# 13_-_ETHERNET_PHY.net
KiCad netlist of a schematic drawn in Altium Designer
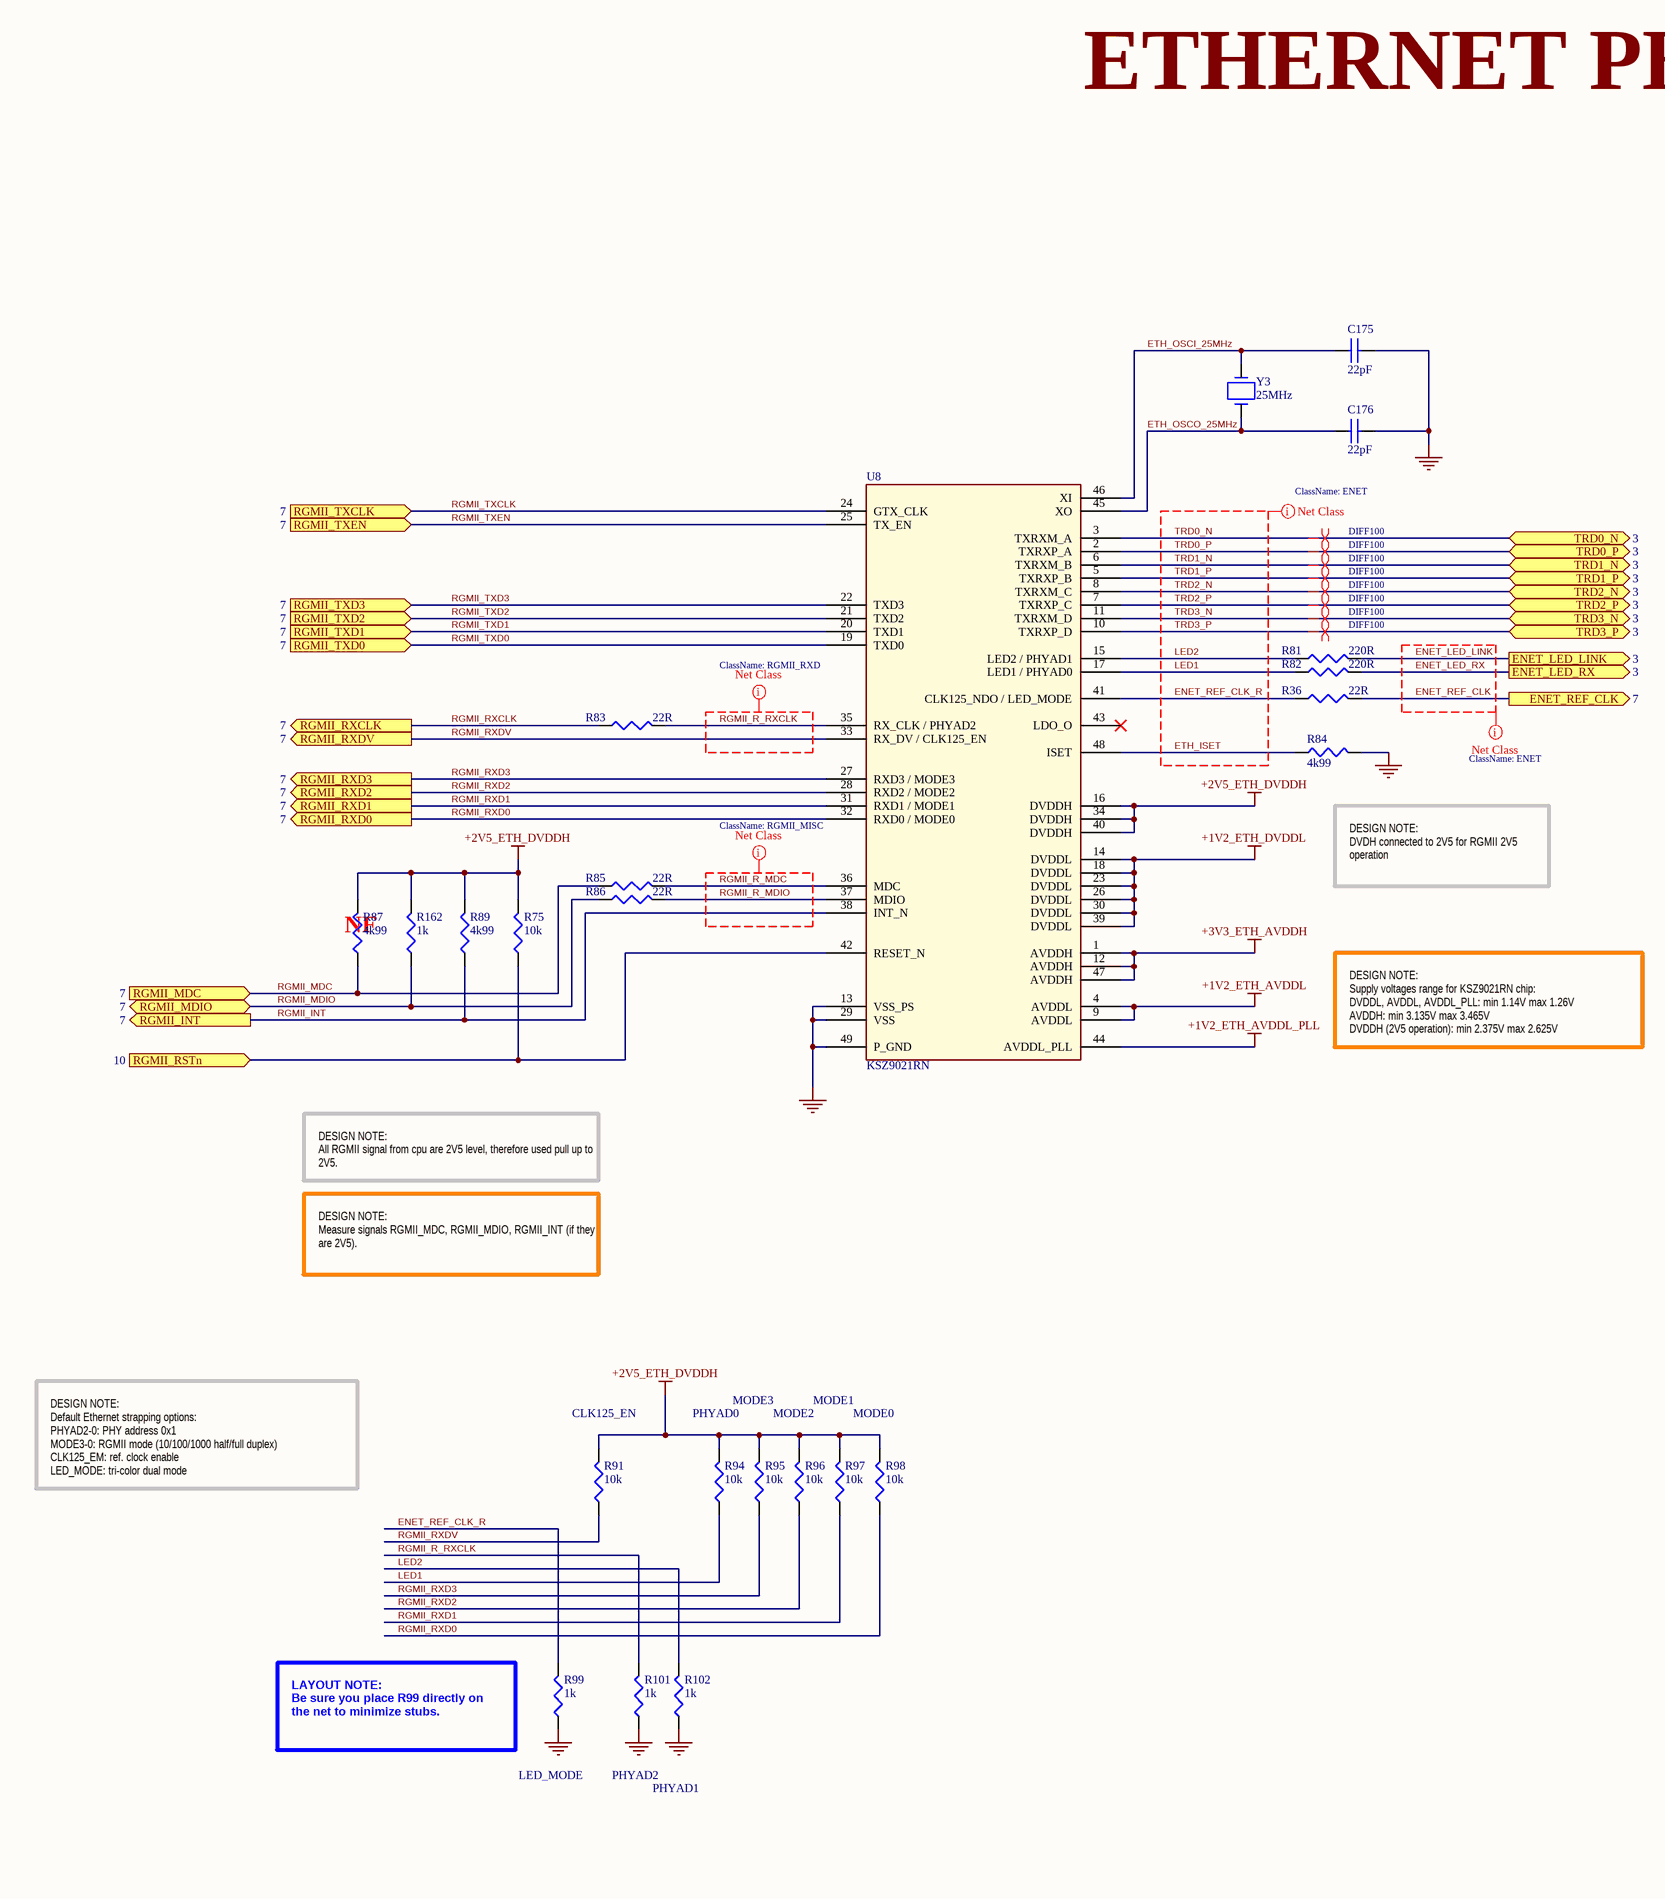
[diagram p0: [13] - ETHERNET PHY.SchDoc, left]
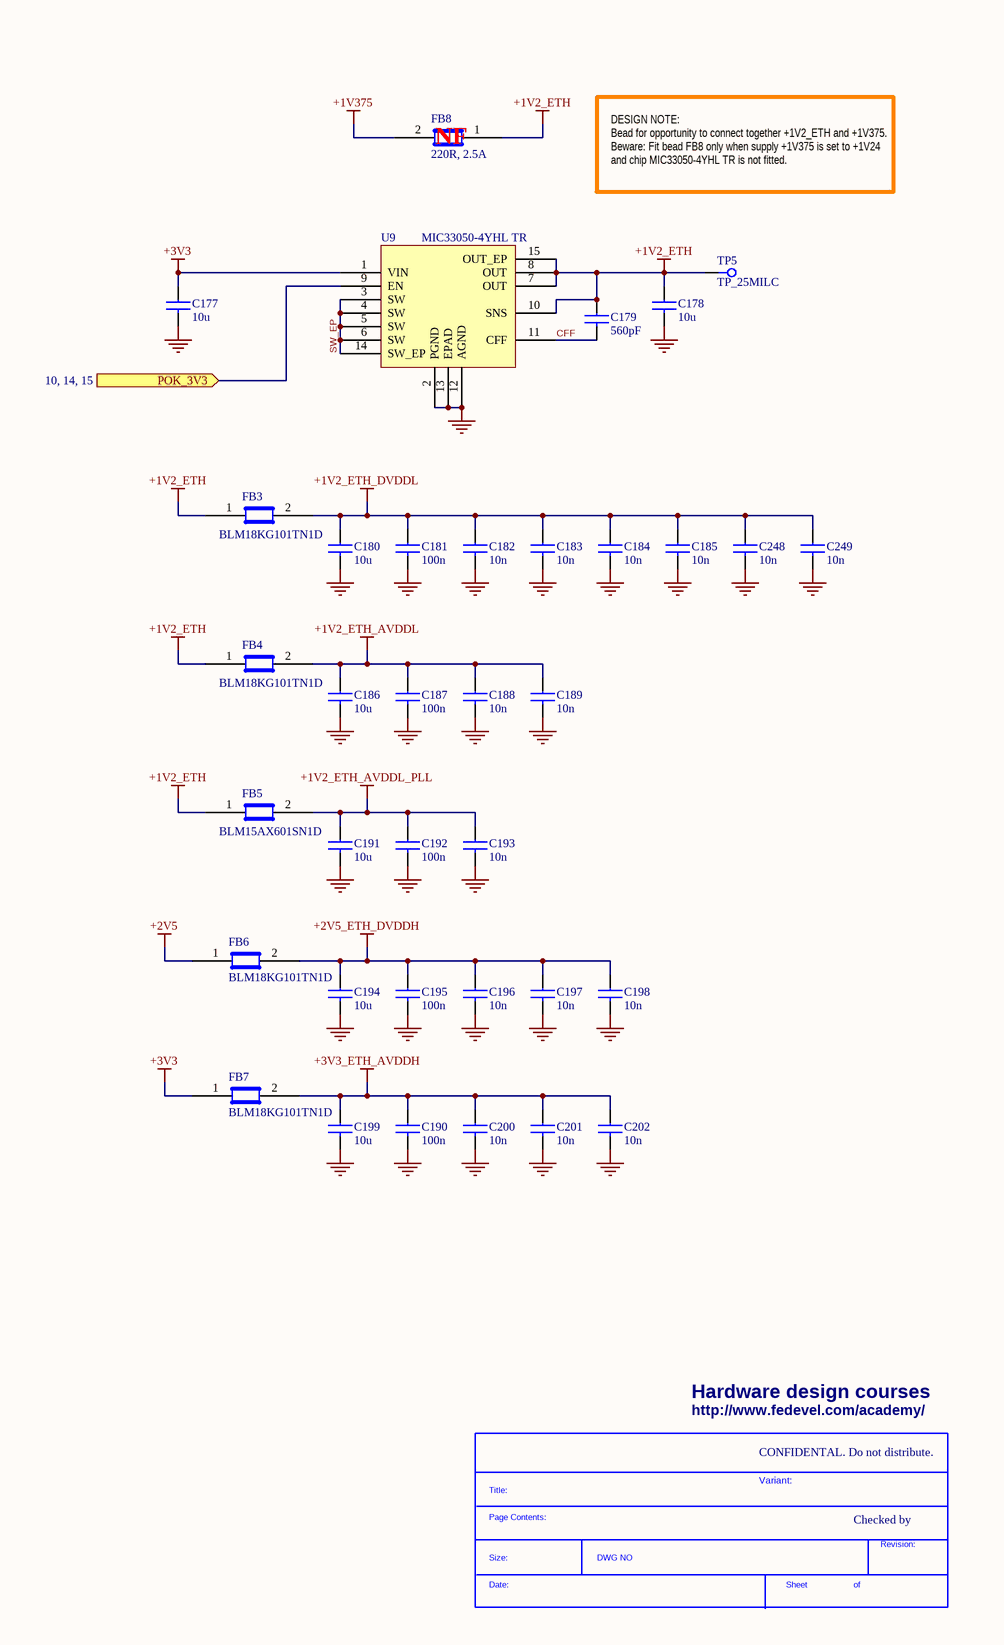
[diagram p1: [13] - ETHERNET PHY.SchDoc, right]

(export (version "E")
  (design (tool "Eeschema 10.0.6"))
  (components
    (comp (ref "C175")
      (value "22pF")
      (footprint "C0402")
      (description "CAP CER 22PF 50V C0G 5% 0402")
      (fields
        (field (name "MANUFACTURER") "TDK Corporation")
        (field (name "MANUFACTURER PART NUMBER") "C1005C0G1H220J")
      )
      (libsource (lib "iMX6 Rex_V1I1") (part "C1005C0G1H220J"))
    )
    (comp (ref "C176")
      (value "22pF")
      (footprint "C0402")
      (description "CAP CER 22PF 50V C0G 5% 0402")
      (fields
        (field (name "MANUFACTURER") "TDK Corporation")
        (field (name "MANUFACTURER PART NUMBER") "C1005C0G1H220J")
      )
      (libsource (lib "iMX6 Rex_V1I1") (part "C1005C0G1H220J"))
    )
    (comp (ref "C177")
      (value "10u")
      (footprint "C0603")
      (description "CAP CER 10UF 6.3V X5R 20% 0603")
      (fields
        (field (name "MANUFACTURER") "TDK Corporation")
        (field (name "MANUFACTURER PART NUMBER") "C1608X5R0J106M")
      )
      (libsource (lib "iMX6 Rex_V1I1") (part "C1608X5R0J106M"))
    )
    (comp (ref "C178")
      (value "10u")
      (footprint "C0603")
      (description "CAP CER 10UF 6.3V X5R 20% 0603")
      (fields
        (field (name "MANUFACTURER") "TDK Corporation")
        (field (name "MANUFACTURER PART NUMBER") "C1608X5R0J106M")
      )
      (libsource (lib "iMX6 Rex_V1I1") (part "C1608X5R0J106M"))
    )
    (comp (ref "C179")
      (value "560pF")
      (footprint "C0402")
      (description "CAP CER 560PF 50V C0G 0402")
      (fields
        (field (name "MANUFACTURER") "Murata Electronics North America")
        (field (name "MANUFACTURER PART NUMBER") "GRM1555C1H561JA01D")
      )
      (libsource (lib "iMX6 Rex_V1I1") (part "GRM1555C1H561JA01D"))
    )
    (comp (ref "C180")
      (value "10u")
      (footprint "C0603")
      (description "CAP CER 10UF 6.3V X5R 20% 0603")
      (fields
        (field (name "MANUFACTURER") "TDK Corporation")
        (field (name "MANUFACTURER PART NUMBER") "C1608X5R0J106M")
      )
      (libsource (lib "iMX6 Rex_V1I1") (part "C1608X5R0J106M"))
    )
    (comp (ref "C181")
      (value "100n")
      (footprint "C0402")
      (description "CAP CER .10UF 50V X5R 10% 0402")
      (fields
        (field (name "MANUFACTURER") "TDK Corporation")
        (field (name "MANUFACTURER PART NUMBER") "C1005X5R1H104K")
      )
      (libsource (lib "iMX6 Rex_V1I1") (part "C1005X5R1H104K"))
    )
    (comp (ref "C182")
      (value "10n")
      (footprint "C0402")
      (description "CAP CER 10000PF 16V X7R 10% 0402")
      (fields
        (field (name "MANUFACTURER") "TDK Corporation")
        (field (name "MANUFACTURER PART NUMBER") "C1005X7R1C103K")
      )
      (libsource (lib "iMX6 Rex_V1I1") (part "C1005X7R1C103K"))
    )
    (comp (ref "C183")
      (value "10n")
      (footprint "C0402")
      (description "CAP CER 10000PF 16V X7R 10% 0402")
      (fields
        (field (name "MANUFACTURER") "TDK Corporation")
        (field (name "MANUFACTURER PART NUMBER") "C1005X7R1C103K")
      )
      (libsource (lib "iMX6 Rex_V1I1") (part "C1005X7R1C103K"))
    )
    (comp (ref "C184")
      (value "10n")
      (footprint "C0402")
      (description "CAP CER 10000PF 16V X7R 10% 0402")
      (fields
        (field (name "MANUFACTURER") "TDK Corporation")
        (field (name "MANUFACTURER PART NUMBER") "C1005X7R1C103K")
      )
      (libsource (lib "iMX6 Rex_V1I1") (part "C1005X7R1C103K"))
    )
    (comp (ref "C185")
      (value "10n")
      (footprint "C0402")
      (description "CAP CER 10000PF 16V X7R 10% 0402")
      (fields
        (field (name "MANUFACTURER") "TDK Corporation")
        (field (name "MANUFACTURER PART NUMBER") "C1005X7R1C103K")
      )
      (libsource (lib "iMX6 Rex_V1I1") (part "C1005X7R1C103K"))
    )
    (comp (ref "C186")
      (value "10u")
      (footprint "C0603")
      (description "CAP CER 10UF 6.3V X5R 20% 0603")
      (fields
        (field (name "MANUFACTURER") "TDK Corporation")
        (field (name "MANUFACTURER PART NUMBER") "C1608X5R0J106M")
      )
      (libsource (lib "iMX6 Rex_V1I1") (part "C1608X5R0J106M"))
    )
    (comp (ref "C187")
      (value "100n")
      (footprint "C0402")
      (description "CAP CER .10UF 50V X5R 10% 0402")
      (fields
        (field (name "MANUFACTURER") "TDK Corporation")
        (field (name "MANUFACTURER PART NUMBER") "C1005X5R1H104K")
      )
      (libsource (lib "iMX6 Rex_V1I1") (part "C1005X5R1H104K"))
    )
    (comp (ref "C188")
      (value "10n")
      (footprint "C0402")
      (description "CAP CER 10000PF 16V X7R 10% 0402")
      (fields
        (field (name "MANUFACTURER") "TDK Corporation")
        (field (name "MANUFACTURER PART NUMBER") "C1005X7R1C103K")
      )
      (libsource (lib "iMX6 Rex_V1I1") (part "C1005X7R1C103K"))
    )
    (comp (ref "C189")
      (value "10n")
      (footprint "C0402")
      (description "CAP CER 10000PF 16V X7R 10% 0402")
      (fields
        (field (name "MANUFACTURER") "TDK Corporation")
        (field (name "MANUFACTURER PART NUMBER") "C1005X7R1C103K")
      )
      (libsource (lib "iMX6 Rex_V1I1") (part "C1005X7R1C103K"))
    )
    (comp (ref "C190")
      (value "100n")
      (footprint "C0402")
      (description "CAP CER .10UF 50V X5R 10% 0402")
      (fields
        (field (name "MANUFACTURER") "TDK Corporation")
        (field (name "MANUFACTURER PART NUMBER") "C1005X5R1H104K")
      )
      (libsource (lib "iMX6 Rex_V1I1") (part "C1005X5R1H104K"))
    )
    (comp (ref "C191")
      (value "10u")
      (footprint "C0603")
      (description "CAP CER 10UF 6.3V X5R 20% 0603")
      (fields
        (field (name "MANUFACTURER") "TDK Corporation")
        (field (name "MANUFACTURER PART NUMBER") "C1608X5R0J106M")
      )
      (libsource (lib "iMX6 Rex_V1I1") (part "C1608X5R0J106M"))
    )
    (comp (ref "C192")
      (value "100n")
      (footprint "C0402")
      (description "CAP CER .10UF 50V X5R 10% 0402")
      (fields
        (field (name "MANUFACTURER") "TDK Corporation")
        (field (name "MANUFACTURER PART NUMBER") "C1005X5R1H104K")
      )
      (libsource (lib "iMX6 Rex_V1I1") (part "C1005X5R1H104K"))
    )
    (comp (ref "C193")
      (value "10n")
      (footprint "C0402")
      (description "CAP CER 10000PF 16V X7R 10% 0402")
      (fields
        (field (name "MANUFACTURER") "TDK Corporation")
        (field (name "MANUFACTURER PART NUMBER") "C1005X7R1C103K")
      )
      (libsource (lib "iMX6 Rex_V1I1") (part "C1005X7R1C103K"))
    )
    (comp (ref "C194")
      (value "10u")
      (footprint "C0603")
      (description "CAP CER 10UF 6.3V X5R 20% 0603")
      (fields
        (field (name "MANUFACTURER") "TDK Corporation")
        (field (name "MANUFACTURER PART NUMBER") "C1608X5R0J106M")
      )
      (libsource (lib "iMX6 Rex_V1I1") (part "C1608X5R0J106M"))
    )
    (comp (ref "C195")
      (value "100n")
      (footprint "C0402")
      (description "CAP CER .10UF 50V X5R 10% 0402")
      (fields
        (field (name "MANUFACTURER") "TDK Corporation")
        (field (name "MANUFACTURER PART NUMBER") "C1005X5R1H104K")
      )
      (libsource (lib "iMX6 Rex_V1I1") (part "C1005X5R1H104K"))
    )
    (comp (ref "C196")
      (value "10n")
      (footprint "C0402")
      (description "CAP CER 10000PF 16V X7R 10% 0402")
      (fields
        (field (name "MANUFACTURER") "TDK Corporation")
        (field (name "MANUFACTURER PART NUMBER") "C1005X7R1C103K")
      )
      (libsource (lib "iMX6 Rex_V1I1") (part "C1005X7R1C103K"))
    )
    (comp (ref "C197")
      (value "10n")
      (footprint "C0402")
      (description "CAP CER 10000PF 16V X7R 10% 0402")
      (fields
        (field (name "MANUFACTURER") "TDK Corporation")
        (field (name "MANUFACTURER PART NUMBER") "C1005X7R1C103K")
      )
      (libsource (lib "iMX6 Rex_V1I1") (part "C1005X7R1C103K"))
    )
    (comp (ref "C198")
      (value "10n")
      (footprint "C0402")
      (description "CAP CER 10000PF 16V X7R 10% 0402")
      (fields
        (field (name "MANUFACTURER") "TDK Corporation")
        (field (name "MANUFACTURER PART NUMBER") "C1005X7R1C103K")
      )
      (libsource (lib "iMX6 Rex_V1I1") (part "C1005X7R1C103K"))
    )
    (comp (ref "C199")
      (value "10u")
      (footprint "C0603")
      (description "CAP CER 10UF 6.3V X5R 20% 0603")
      (fields
        (field (name "MANUFACTURER") "TDK Corporation")
        (field (name "MANUFACTURER PART NUMBER") "C1608X5R0J106M")
      )
      (libsource (lib "iMX6 Rex_V1I1") (part "C1608X5R0J106M"))
    )
    (comp (ref "C200")
      (value "10n")
      (footprint "C0402")
      (description "CAP CER 10000PF 16V X7R 10% 0402")
      (fields
        (field (name "MANUFACTURER") "TDK Corporation")
        (field (name "MANUFACTURER PART NUMBER") "C1005X7R1C103K")
      )
      (libsource (lib "iMX6 Rex_V1I1") (part "C1005X7R1C103K"))
    )
    (comp (ref "C201")
      (value "10n")
      (footprint "C0402")
      (description "CAP CER 10000PF 16V X7R 10% 0402")
      (fields
        (field (name "MANUFACTURER") "TDK Corporation")
        (field (name "MANUFACTURER PART NUMBER") "C1005X7R1C103K")
      )
      (libsource (lib "iMX6 Rex_V1I1") (part "C1005X7R1C103K"))
    )
    (comp (ref "C202")
      (value "10n")
      (footprint "C0402")
      (description "CAP CER 10000PF 16V X7R 10% 0402")
      (fields
        (field (name "MANUFACTURER") "TDK Corporation")
        (field (name "MANUFACTURER PART NUMBER") "C1005X7R1C103K")
      )
      (libsource (lib "iMX6 Rex_V1I1") (part "C1005X7R1C103K"))
    )
    (comp (ref "C248")
      (value "10n")
      (footprint "C0402")
      (description "CAP CER 10000PF 16V X7R 10% 0402")
      (fields
        (field (name "MANUFACTURER") "TDK Corporation")
        (field (name "MANUFACTURER PART NUMBER") "C1005X7R1C103K")
      )
      (libsource (lib "iMX6 Rex_V1I1") (part "C1005X7R1C103K"))
    )
    (comp (ref "C249")
      (value "10n")
      (footprint "C0402")
      (description "CAP CER 10000PF 16V X7R 10% 0402")
      (fields
        (field (name "MANUFACTURER") "TDK Corporation")
        (field (name "MANUFACTURER PART NUMBER") "C1005X7R1C103K")
      )
      (libsource (lib "iMX6 Rex_V1I1") (part "C1005X7R1C103K"))
    )
    (comp (ref "FB3")
      (value "BLM18KG101TN1D")
      (footprint "C0603")
      (description "FERRITE CHIP 100 OHM BEAD 0603 3A")
      (fields (field (name "MANUFACTURER") "Murata Electronics North America"))
      (libsource (lib "iMX6 Rex_V1I1") (part "BLM18KG101TN1D"))
    )
    (comp (ref "FB4")
      (value "BLM18KG101TN1D")
      (footprint "C0603")
      (description "FERRITE CHIP 100 OHM BEAD 0603 3A")
      (fields (field (name "MANUFACTURER") "Murata Electronics North America"))
      (libsource (lib "iMX6 Rex_V1I1") (part "BLM18KG101TN1D"))
    )
    (comp (ref "FB5")
      (value "BLM15AX601SN1D")
      (footprint "C0402")
      (description "FERRITE CHIP 600 OHM 0402 420mA")
      (fields (field (name "MANUFACTURER") "Murata Electronics North America"))
      (libsource (lib "iMX6 Rex_V1I1") (part "BLM15AX601SN1D"))
    )
    (comp (ref "FB6")
      (value "BLM18KG101TN1D")
      (footprint "C0603")
      (description "FERRITE CHIP 100 OHM BEAD 0603 3A")
      (fields (field (name "MANUFACTURER") "Murata Electronics North America"))
      (libsource (lib "iMX6 Rex_V1I1") (part "BLM18KG101TN1D"))
    )
    (comp (ref "FB7")
      (value "BLM18KG101TN1D")
      (footprint "C0603")
      (description "FERRITE CHIP 100 OHM BEAD 0603 3A")
      (fields (field (name "MANUFACTURER") "Murata Electronics North America"))
      (libsource (lib "iMX6 Rex_V1I1") (part "BLM18KG101TN1D"))
    )
    (comp (ref "FB8")
      (value "220R, 2.5A")
      (footprint "C0603")
      (description "FERRITE CHIP 220 OHM 2500MA 0603")
      (fields
        (field (name "MANUFACTURER") "Murata Electronics North America")
        (field (name "MANUFACTURER PART NUMBER") "BLM18SG221TN1D")
        (field (name ".CHECKED PCB") "RF")
        (field (name ".CHECKED SCH") "RF")
      )
      (libsource (lib "iMX6 Rex_V1I1") (part "BLM18SG221TN1D"))
    )
    (comp (ref "R36")
      (value "22R")
      (footprint "R0402")
      (description "RES 22.0 OHM 1/16W 1% 0402 SMD")
      (fields
        (field (name "MANUFACTURER") "Yageo")
        (field (name "MANUFACTURER PART NUMBER") "RC0402FR-0722RL")
      )
      (libsource (lib "iMX6 Rex_V1I1") (part "RC0402FR-0722RL"))
    )
    (comp (ref "R75")
      (value "10k")
      (footprint "R0402")
      (description "RES 10.0K OHM 1/16W 1% 0402 SMD")
      (fields
        (field (name "MANUFACTURER") "Yageo")
        (field (name "MANUFACTURER PART NUMBER") "RC0402FR-0710KL")
      )
      (libsource (lib "iMX6 Rex_V1I1") (part "RC0402FR-0710KL"))
    )
    (comp (ref "R81")
      (value "220R")
      (footprint "R0402")
      (description "RES 220 OHM 1/16W 1% 0402 SMD")
      (fields
        (field (name "MANUFACTURER") "Yageo")
        (field (name "MANUFACTURER PART NUMBER") "RC0402FR-07220RL")
      )
      (libsource (lib "iMX6 Rex_V1I1") (part "RC0402FR-07220RL"))
    )
    (comp (ref "R82")
      (value "220R")
      (footprint "R0402")
      (description "RES 220 OHM 1/16W 1% 0402 SMD")
      (fields
        (field (name "MANUFACTURER") "Yageo")
        (field (name "MANUFACTURER PART NUMBER") "RC0402FR-07220RL")
      )
      (libsource (lib "iMX6 Rex_V1I1") (part "RC0402FR-07220RL"))
    )
    (comp (ref "R83")
      (value "22R")
      (footprint "R0402")
      (description "RES 22.0 OHM 1/16W 1% 0402 SMD")
      (fields
        (field (name "MANUFACTURER") "Yageo")
        (field (name "MANUFACTURER PART NUMBER") "RC0402FR-0722RL")
      )
      (libsource (lib "iMX6 Rex_V1I1") (part "RC0402FR-0722RL"))
    )
    (comp (ref "R84")
      (value "4k99")
      (footprint "R0402")
      (description "RES TF 4.99K OHM 1% 1/16W 0402")
      (fields
        (field (name "MANUFACTURER") "Stackpole Electronics Inc")
        (field (name "MANUFACTURER PART NUMBER") "RMCF0402FT4K99")
      )
      (libsource (lib "iMX6 Rex_V1I1") (part "RMCF0402FT4K99"))
    )
    (comp (ref "R85")
      (value "22R")
      (footprint "R0402")
      (description "RES 22.0 OHM 1/16W 1% 0402 SMD")
      (fields
        (field (name "MANUFACTURER") "Yageo")
        (field (name "MANUFACTURER PART NUMBER") "RC0402FR-0722RL")
      )
      (libsource (lib "iMX6 Rex_V1I1") (part "RC0402FR-0722RL"))
    )
    (comp (ref "R86")
      (value "22R")
      (footprint "R0402")
      (description "RES 22.0 OHM 1/16W 1% 0402 SMD")
      (fields
        (field (name "MANUFACTURER") "Yageo")
        (field (name "MANUFACTURER PART NUMBER") "RC0402FR-0722RL")
      )
      (libsource (lib "iMX6 Rex_V1I1") (part "RC0402FR-0722RL"))
    )
    (comp (ref "R87")
      (value "4k99")
      (footprint "R0402")
      (description "RES TF 4.99K OHM 1% 1/16W 0402")
      (fields
        (field (name "MANUFACTURER") "Stackpole Electronics Inc")
        (field (name "MANUFACTURER PART NUMBER") "RMCF0402FT4K99")
      )
      (libsource (lib "iMX6 Rex_V1I1") (part "RMCF0402FT4K99"))
    )
    (comp (ref "R89")
      (value "4k99")
      (footprint "R0402")
      (description "RES TF 4.99K OHM 1% 1/16W 0402")
      (fields
        (field (name "MANUFACTURER") "Stackpole Electronics Inc")
        (field (name "MANUFACTURER PART NUMBER") "RMCF0402FT4K99")
      )
      (libsource (lib "iMX6 Rex_V1I1") (part "RMCF0402FT4K99"))
    )
    (comp (ref "R91")
      (value "10k")
      (footprint "R0402")
      (description "RES 10.0K OHM 1/16W 1% 0402 SMD")
      (fields
        (field (name "MANUFACTURER") "Yageo")
        (field (name "MANUFACTURER PART NUMBER") "RC0402FR-0710KL")
      )
      (libsource (lib "iMX6 Rex_V1I1") (part "RC0402FR-0710KL"))
    )
    (comp (ref "R94")
      (value "10k")
      (footprint "R0402")
      (description "RES 10.0K OHM 1/16W 1% 0402 SMD")
      (fields
        (field (name "MANUFACTURER") "Yageo")
        (field (name "MANUFACTURER PART NUMBER") "RC0402FR-0710KL")
      )
      (libsource (lib "iMX6 Rex_V1I1") (part "RC0402FR-0710KL"))
    )
    (comp (ref "R95")
      (value "10k")
      (footprint "R0402")
      (description "RES 10.0K OHM 1/16W 1% 0402 SMD")
      (fields
        (field (name "MANUFACTURER") "Yageo")
        (field (name "MANUFACTURER PART NUMBER") "RC0402FR-0710KL")
      )
      (libsource (lib "iMX6 Rex_V1I1") (part "RC0402FR-0710KL"))
    )
    (comp (ref "R96")
      (value "10k")
      (footprint "R0402")
      (description "RES 10.0K OHM 1/16W 1% 0402 SMD")
      (fields
        (field (name "MANUFACTURER") "Yageo")
        (field (name "MANUFACTURER PART NUMBER") "RC0402FR-0710KL")
      )
      (libsource (lib "iMX6 Rex_V1I1") (part "RC0402FR-0710KL"))
    )
    (comp (ref "R97")
      (value "10k")
      (footprint "R0402")
      (description "RES 10.0K OHM 1/16W 1% 0402 SMD")
      (fields
        (field (name "MANUFACTURER") "Yageo")
        (field (name "MANUFACTURER PART NUMBER") "RC0402FR-0710KL")
      )
      (libsource (lib "iMX6 Rex_V1I1") (part "RC0402FR-0710KL"))
    )
    (comp (ref "R98")
      (value "10k")
      (footprint "R0402")
      (description "RES 10.0K OHM 1/16W 1% 0402 SMD")
      (fields
        (field (name "MANUFACTURER") "Yageo")
        (field (name "MANUFACTURER PART NUMBER") "RC0402FR-0710KL")
      )
      (libsource (lib "iMX6 Rex_V1I1") (part "RC0402FR-0710KL"))
    )
    (comp (ref "R99")
      (value "1k")
      (footprint "R0402")
      (description "RES 1.00K OHM 1/16W 1% 0402 SMD")
      (fields
        (field (name "MANUFACTURER") "Yageo")
        (field (name "MANUFACTURER PART NUMBER") "RC0402FR-071KL")
      )
      (libsource (lib "iMX6 Rex_V1I1") (part "RC0402FR-071KL"))
    )
    (comp (ref "R101")
      (value "1k")
      (footprint "R0402")
      (description "RES 1.00K OHM 1/16W 1% 0402 SMD")
      (fields
        (field (name "MANUFACTURER") "Yageo")
        (field (name "MANUFACTURER PART NUMBER") "RC0402FR-071KL")
      )
      (libsource (lib "iMX6 Rex_V1I1") (part "RC0402FR-071KL"))
    )
    (comp (ref "R102")
      (value "1k")
      (footprint "R0402")
      (description "RES 1.00K OHM 1/16W 1% 0402 SMD")
      (fields
        (field (name "MANUFACTURER") "Yageo")
        (field (name "MANUFACTURER PART NUMBER") "RC0402FR-071KL")
      )
      (libsource (lib "iMX6 Rex_V1I1") (part "RC0402FR-071KL"))
    )
    (comp (ref "R162")
      (value "1k")
      (footprint "R0402")
      (description "RES 1.00K OHM 1/16W 1% 0402 SMD")
      (fields
        (field (name "MANUFACTURER") "Yageo")
        (field (name "MANUFACTURER PART NUMBER") "RC0402FR-071KL")
      )
      (libsource (lib "iMX6 Rex_V1I1") (part "RC0402FR-071KL"))
    )
    (comp (ref "TP5")
      (value "TP_25MILC")
      (footprint "TP_25C")
      (description "Test Point 25mil")
      (libsource (lib "iMX6 Rex_V1I1") (part "TP_25MILC"))
    )
    (comp (ref "U8")
      (value "KSZ9021RN")
      (footprint "QFN48_7MMX7MM")
      (description "IC TXRX 10/100/1000 SGL 48QFN")
      (fields
        (field (name "MANUFACTURER") "Micrel Inc")
        (field (name ".CREATOR") "MM")
        (field (name ".CHECKED PCB") "MM, checked by RF")
        (field (name ".CHECKED SCH") "MM, checked by RF")
      )
      (libsource (lib "iMX6 Rex_V1I1") (part "KSZ9021RN"))
    )
    (comp (ref "U9")
      (value "MIC33050-4YHL TR")
      (footprint "MLF_3x3_12PINS")
      (description "IC PWM REG 600mA 1.2V 12-MLF")
      (fields (field (name "MANUFACTURER") "Micrel Inc"))
      (libsource (lib "iMX6 Rex_V1I1") (part "MIC33050-4YHL TR"))
    )
    (comp (ref "Y3")
      (value "25MHz")
      (footprint "ABM7_v1_1")
      (description "CRYSTAL 25.0000 MHZ 18PF SMD")
      (fields
        (field (name "MANUFACTURER") "Abracon Corporation")
        (field (name "MANUFACTURER PART NUMBER") "ABM7-25.000MHZ-D-2-Y-T")
        (field (name ".CHECKED PCB") "RF used by MM")
        (field (name ".CHECKED SCH") "RF used by MM")
      )
      (libsource (lib "iMX6 Rex_V1I1") (part "ABM7-25.000MHZ-D-2-Y-T V1.1"))
    )
  )
  (nets
    (net (code "1") (name "+1V2_ETH") (class "Default")
      (node (ref "C178") (pin "1") (pinfunction "1_1") (pintype "passive"))
      (node (ref "C179") (pin "1") (pinfunction "1_1") (pintype "passive"))
      (node (ref "FB3") (pin "1") (pinfunction "1_1") (pintype "passive"))
      (node (ref "FB4") (pin "1") (pinfunction "1_1") (pintype "passive"))
      (node (ref "FB5") (pin "1") (pinfunction "1_1") (pintype "passive"))
      (node (ref "FB8") (pin "1") (pinfunction "1_1") (pintype "passive"))
      (node (ref "TP5") (pin "1") (pinfunction "1_1") (pintype "passive"))
      (node (ref "U9") (pin "10") (pinfunction "SNS_10") (pintype "passive"))
      (node (ref "U9") (pin "15") (pinfunction "OUT_EP_15") (pintype "passive"))
      (node (ref "U9") (pin "7") (pinfunction "OUT_7") (pintype "passive"))
      (node (ref "U9") (pin "8") (pinfunction "OUT_8") (pintype "passive"))
    )
    (net (code "2") (name "+1V2_ETH_AVDDL") (class "Default")
      (node (ref "C186") (pin "1") (pinfunction "1_1") (pintype "passive"))
      (node (ref "C187") (pin "1") (pinfunction "1_1") (pintype "passive"))
      (node (ref "C188") (pin "1") (pinfunction "1_1") (pintype "passive"))
      (node (ref "C189") (pin "1") (pinfunction "1_1") (pintype "passive"))
      (node (ref "FB4") (pin "2") (pinfunction "2_2") (pintype "passive"))
      (node (ref "U8") (pin "4") (pinfunction "AVDDL_4") (pintype "passive"))
      (node (ref "U8") (pin "9") (pinfunction "AVDDL_9") (pintype "passive"))
    )
    (net (code "3") (name "+1V2_ETH_AVDDL_PLL") (class "Default")
      (node (ref "C191") (pin "1") (pinfunction "1_1") (pintype "passive"))
      (node (ref "C192") (pin "1") (pinfunction "1_1") (pintype "passive"))
      (node (ref "C193") (pin "1") (pinfunction "1_1") (pintype "passive"))
      (node (ref "FB5") (pin "2") (pinfunction "2_2") (pintype "passive"))
      (node (ref "U8") (pin "44") (pinfunction "AVDDL_PLL_44") (pintype "passive"))
    )
    (net (code "4") (name "+1V2_ETH_DVDDL") (class "Default")
      (node (ref "C180") (pin "1") (pinfunction "1_1") (pintype "passive"))
      (node (ref "C181") (pin "1") (pinfunction "1_1") (pintype "passive"))
      (node (ref "C182") (pin "1") (pinfunction "1_1") (pintype "passive"))
      (node (ref "C183") (pin "1") (pinfunction "1_1") (pintype "passive"))
      (node (ref "C184") (pin "1") (pinfunction "1_1") (pintype "passive"))
      (node (ref "C185") (pin "1") (pinfunction "1_1") (pintype "passive"))
      (node (ref "C248") (pin "1") (pinfunction "1_1") (pintype "passive"))
      (node (ref "C249") (pin "1") (pinfunction "1_1") (pintype "passive"))
      (node (ref "FB3") (pin "2") (pinfunction "2_2") (pintype "passive"))
      (node (ref "U8") (pin "14") (pinfunction "DVDDL_14") (pintype "passive"))
      (node (ref "U8") (pin "18") (pinfunction "DVDDL_18") (pintype "passive"))
      (node (ref "U8") (pin "23") (pinfunction "DVDDL_23") (pintype "passive"))
      (node (ref "U8") (pin "26") (pinfunction "DVDDL_26") (pintype "passive"))
      (node (ref "U8") (pin "30") (pinfunction "DVDDL_30") (pintype "passive"))
      (node (ref "U8") (pin "39") (pinfunction "DVDDL_39") (pintype "passive"))
    )
    (net (code "5") (name "+1V375") (class "Default")
      (node (ref "FB8") (pin "2") (pinfunction "2_2") (pintype "passive"))
    )
    (net (code "6") (name "+2V5") (class "Default")
      (node (ref "FB6") (pin "1") (pinfunction "1_1") (pintype "passive"))
    )
    (net (code "7") (name "+2V5_ETH_DVDDH") (class "Default")
      (node (ref "C194") (pin "1") (pinfunction "1_1") (pintype "passive"))
      (node (ref "C195") (pin "1") (pinfunction "1_1") (pintype "passive"))
      (node (ref "C196") (pin "1") (pinfunction "1_1") (pintype "passive"))
      (node (ref "C197") (pin "1") (pinfunction "1_1") (pintype "passive"))
      (node (ref "C198") (pin "1") (pinfunction "1_1") (pintype "passive"))
      (node (ref "FB6") (pin "2") (pinfunction "2_2") (pintype "passive"))
      (node (ref "R162") (pin "2") (pinfunction "2_2") (pintype "passive"))
      (node (ref "R75") (pin "2") (pinfunction "2_2") (pintype "passive"))
      (node (ref "R87") (pin "2") (pinfunction "2_2") (pintype "passive"))
      (node (ref "R89") (pin "2") (pinfunction "2_2") (pintype "passive"))
      (node (ref "R91") (pin "2") (pinfunction "2_2") (pintype "passive"))
      (node (ref "R94") (pin "2") (pinfunction "2_2") (pintype "passive"))
      (node (ref "R95") (pin "2") (pinfunction "2_2") (pintype "passive"))
      (node (ref "R96") (pin "2") (pinfunction "2_2") (pintype "passive"))
      (node (ref "R97") (pin "2") (pinfunction "2_2") (pintype "passive"))
      (node (ref "R98") (pin "2") (pinfunction "2_2") (pintype "passive"))
      (node (ref "U8") (pin "16") (pinfunction "DVDDH_16") (pintype "passive"))
      (node (ref "U8") (pin "34") (pinfunction "DVDDH_34") (pintype "passive"))
      (node (ref "U8") (pin "40") (pinfunction "DVDDH_40") (pintype "passive"))
    )
    (net (code "8") (name "+3V3") (class "Default")
      (node (ref "C177") (pin "1") (pinfunction "1_1") (pintype "passive"))
      (node (ref "FB7") (pin "1") (pinfunction "1_1") (pintype "passive"))
      (node (ref "U9") (pin "1") (pinfunction "VIN_1") (pintype "passive"))
    )
    (net (code "9") (name "+3V3_ETH_AVDDH") (class "Default")
      (node (ref "C190") (pin "1") (pinfunction "1_1") (pintype "passive"))
      (node (ref "C199") (pin "1") (pinfunction "1_1") (pintype "passive"))
      (node (ref "C200") (pin "1") (pinfunction "1_1") (pintype "passive"))
      (node (ref "C201") (pin "1") (pinfunction "1_1") (pintype "passive"))
      (node (ref "C202") (pin "1") (pinfunction "1_1") (pintype "passive"))
      (node (ref "FB7") (pin "2") (pinfunction "2_2") (pintype "passive"))
      (node (ref "U8") (pin "1") (pinfunction "AVDDH_1") (pintype "passive"))
      (node (ref "U8") (pin "12") (pinfunction "AVDDH_12") (pintype "passive"))
      (node (ref "U8") (pin "47") (pinfunction "AVDDH_47") (pintype "passive"))
    )
    (net (code "10") (name "/CFF") (class "Default")
      (node (ref "C179") (pin "2") (pinfunction "2_2") (pintype "passive"))
      (node (ref "U9") (pin "11") (pinfunction "CFF_11") (pintype "passive"))
    )
    (net (code "11") (name "/ENET_LED_LINK") (class "Default")
      (node (ref "R81") (pin "2") (pinfunction "2_2") (pintype "passive"))
    )
    (net (code "12") (name "/ENET_LED_RX") (class "Default")
      (node (ref "R82") (pin "2") (pinfunction "2_2") (pintype "passive"))
    )
    (net (code "13") (name "/ENET_REF_CLK") (class "Default")
      (node (ref "R36") (pin "2") (pinfunction "2_2") (pintype "passive"))
    )
    (net (code "14") (name "/ENET_REF_CLK_R") (class "Default")
      (node (ref "R36") (pin "1") (pinfunction "1_1") (pintype "passive"))
      (node (ref "R99") (pin "2") (pinfunction "2_2") (pintype "passive"))
      (node (ref "U8") (pin "41") (pinfunction "CLK125_NDO_/_LED_MODE_41") (pintype "passive"))
    )
    (net (code "15") (name "/ETH_ISET") (class "Default")
      (node (ref "R84") (pin "1") (pinfunction "1_1") (pintype "passive"))
      (node (ref "U8") (pin "48") (pinfunction "ISET_48") (pintype "passive"))
    )
    (net (code "16") (name "/ETH_OSCI_25MHz") (class "Default")
      (node (ref "C175") (pin "1") (pinfunction "1_1") (pintype "passive"))
      (node (ref "U8") (pin "46") (pinfunction "XI_46") (pintype "passive"))
      (node (ref "Y3") (pin "2") (pinfunction "2_2") (pintype "passive"))
    )
    (net (code "17") (name "/ETH_OSCO_25MHz") (class "Default")
      (node (ref "C176") (pin "1") (pinfunction "1_1") (pintype "passive"))
      (node (ref "U8") (pin "45") (pinfunction "XO_45") (pintype "passive"))
      (node (ref "Y3") (pin "1") (pinfunction "1_1") (pintype "passive"))
    )
    (net (code "18") (name "/LED1") (class "Default")
      (node (ref "R82") (pin "1") (pinfunction "1_1") (pintype "passive"))
      (node (ref "R94") (pin "1") (pinfunction "1_1") (pintype "passive"))
      (node (ref "U8") (pin "17") (pinfunction "LED1_/_PHYAD0_17") (pintype "passive"))
    )
    (net (code "19") (name "/LED2") (class "Default")
      (node (ref "R102") (pin "2") (pinfunction "2_2") (pintype "passive"))
      (node (ref "R81") (pin "1") (pinfunction "1_1") (pintype "passive"))
      (node (ref "U8") (pin "15") (pinfunction "LED2_/_PHYAD1_15") (pintype "passive"))
    )
    (net (code "20") (name "/POK_3V3") (class "Default")
      (node (ref "U9") (pin "9") (pinfunction "EN_9") (pintype "passive"))
    )
    (net (code "21") (name "/RGMII_INT") (class "Default")
      (node (ref "R89") (pin "1") (pinfunction "1_1") (pintype "passive"))
      (node (ref "U8") (pin "38") (pinfunction "INT_N_38") (pintype "passive"))
    )
    (net (code "22") (name "/RGMII_MDC") (class "Default")
      (node (ref "R85") (pin "1") (pinfunction "1_1") (pintype "passive"))
      (node (ref "R87") (pin "1") (pinfunction "1_1") (pintype "passive"))
    )
    (net (code "23") (name "/RGMII_MDIO") (class "Default")
      (node (ref "R162") (pin "1") (pinfunction "1_1") (pintype "passive"))
      (node (ref "R86") (pin "1") (pinfunction "1_1") (pintype "passive"))
    )
    (net (code "24") (name "/RGMII_RSTn") (class "Default")
      (node (ref "R75") (pin "1") (pinfunction "1_1") (pintype "passive"))
      (node (ref "U8") (pin "42") (pinfunction "RESET_N_42") (pintype "passive"))
    )
    (net (code "25") (name "/RGMII_RXCLK") (class "Default")
      (node (ref "R83") (pin "1") (pinfunction "1_1") (pintype "passive"))
    )
    (net (code "26") (name "/RGMII_RXD0") (class "Default")
      (node (ref "R98") (pin "1") (pinfunction "1_1") (pintype "passive"))
      (node (ref "U8") (pin "32") (pinfunction "RXD0_/_MODE0_32") (pintype "passive"))
    )
    (net (code "27") (name "/RGMII_RXD1") (class "Default")
      (node (ref "R97") (pin "1") (pinfunction "1_1") (pintype "passive"))
      (node (ref "U8") (pin "31") (pinfunction "RXD1_/_MODE1_31") (pintype "passive"))
    )
    (net (code "28") (name "/RGMII_RXD2") (class "Default")
      (node (ref "R96") (pin "1") (pinfunction "1_1") (pintype "passive"))
      (node (ref "U8") (pin "28") (pinfunction "RXD2_/_MODE2_28") (pintype "passive"))
    )
    (net (code "29") (name "/RGMII_RXD3") (class "Default")
      (node (ref "R95") (pin "1") (pinfunction "1_1") (pintype "passive"))
      (node (ref "U8") (pin "27") (pinfunction "RXD3_/_MODE3_27") (pintype "passive"))
    )
    (net (code "30") (name "/RGMII_RXDV") (class "Default")
      (node (ref "R91") (pin "1") (pinfunction "1_1") (pintype "passive"))
      (node (ref "U8") (pin "33") (pinfunction "RX_DV_/_CLK125_EN_33") (pintype "passive"))
    )
    (net (code "31") (name "/RGMII_R_MDC") (class "Default")
      (node (ref "R85") (pin "2") (pinfunction "2_2") (pintype "passive"))
      (node (ref "U8") (pin "36") (pinfunction "MDC_36") (pintype "passive"))
    )
    (net (code "32") (name "/RGMII_R_MDIO") (class "Default")
      (node (ref "R86") (pin "2") (pinfunction "2_2") (pintype "passive"))
      (node (ref "U8") (pin "37") (pinfunction "MDIO_37") (pintype "passive"))
    )
    (net (code "33") (name "/RGMII_R_RXCLK") (class "Default")
      (node (ref "R101") (pin "2") (pinfunction "2_2") (pintype "passive"))
      (node (ref "R83") (pin "2") (pinfunction "2_2") (pintype "passive"))
      (node (ref "U8") (pin "35") (pinfunction "RX_CLK_/_PHYAD2_35") (pintype "passive"))
    )
    (net (code "34") (name "/RGMII_TXCLK") (class "Default")
      (node (ref "U8") (pin "24") (pinfunction "GTX_CLK_24") (pintype "passive"))
    )
    (net (code "35") (name "/RGMII_TXD0") (class "Default")
      (node (ref "U8") (pin "19") (pinfunction "TXD0_19") (pintype "passive"))
    )
    (net (code "36") (name "/RGMII_TXD1") (class "Default")
      (node (ref "U8") (pin "20") (pinfunction "TXD1_20") (pintype "passive"))
    )
    (net (code "37") (name "/RGMII_TXD2") (class "Default")
      (node (ref "U8") (pin "21") (pinfunction "TXD2_21") (pintype "passive"))
    )
    (net (code "38") (name "/RGMII_TXD3") (class "Default")
      (node (ref "U8") (pin "22") (pinfunction "TXD3_22") (pintype "passive"))
    )
    (net (code "39") (name "/RGMII_TXEN") (class "Default")
      (node (ref "U8") (pin "25") (pinfunction "TX_EN_25") (pintype "passive"))
    )
    (net (code "40") (name "/SW_EP") (class "Default")
      (node (ref "U9") (pin "14") (pinfunction "SW_EP_14") (pintype "passive"))
      (node (ref "U9") (pin "3") (pinfunction "SW_3") (pintype "passive"))
      (node (ref "U9") (pin "4") (pinfunction "SW_4") (pintype "passive"))
      (node (ref "U9") (pin "5") (pinfunction "SW_5") (pintype "passive"))
      (node (ref "U9") (pin "6") (pinfunction "SW_6") (pintype "passive"))
    )
    (net (code "41") (name "/TRD0_N") (class "Default")
      (node (ref "U8") (pin "3") (pinfunction "TXRXM_A_3") (pintype "passive"))
    )
    (net (code "42") (name "/TRD0_P") (class "Default")
      (node (ref "U8") (pin "2") (pinfunction "TXRXP_A_2") (pintype "passive"))
    )
    (net (code "43") (name "/TRD1_N") (class "Default")
      (node (ref "U8") (pin "6") (pinfunction "TXRXM_B_6") (pintype "passive"))
    )
    (net (code "44") (name "/TRD1_P") (class "Default")
      (node (ref "U8") (pin "5") (pinfunction "TXRXP_B_5") (pintype "passive"))
    )
    (net (code "45") (name "/TRD2_N") (class "Default")
      (node (ref "U8") (pin "8") (pinfunction "TXRXM_C_8") (pintype "passive"))
    )
    (net (code "46") (name "/TRD2_P") (class "Default")
      (node (ref "U8") (pin "7") (pinfunction "TXRXP_C_7") (pintype "passive"))
    )
    (net (code "47") (name "/TRD3_N") (class "Default")
      (node (ref "U8") (pin "11") (pinfunction "TXRXM_D_11") (pintype "passive"))
    )
    (net (code "48") (name "/TRD3_P") (class "Default")
      (node (ref "U8") (pin "10") (pinfunction "TXRXP_D_10") (pintype "passive"))
    )
    (net (code "49") (name "GND") (class "Default")
      (node (ref "C175") (pin "2") (pinfunction "2_2") (pintype "passive"))
      (node (ref "C176") (pin "2") (pinfunction "2_2") (pintype "passive"))
      (node (ref "C177") (pin "2") (pinfunction "2_2") (pintype "passive"))
      (node (ref "C178") (pin "2") (pinfunction "2_2") (pintype "passive"))
      (node (ref "C180") (pin "2") (pinfunction "2_2") (pintype "passive"))
      (node (ref "C181") (pin "2") (pinfunction "2_2") (pintype "passive"))
      (node (ref "C182") (pin "2") (pinfunction "2_2") (pintype "passive"))
      (node (ref "C183") (pin "2") (pinfunction "2_2") (pintype "passive"))
      (node (ref "C184") (pin "2") (pinfunction "2_2") (pintype "passive"))
      (node (ref "C185") (pin "2") (pinfunction "2_2") (pintype "passive"))
      (node (ref "C186") (pin "2") (pinfunction "2_2") (pintype "passive"))
      (node (ref "C187") (pin "2") (pinfunction "2_2") (pintype "passive"))
      (node (ref "C188") (pin "2") (pinfunction "2_2") (pintype "passive"))
      (node (ref "C189") (pin "2") (pinfunction "2_2") (pintype "passive"))
      (node (ref "C190") (pin "2") (pinfunction "2_2") (pintype "passive"))
      (node (ref "C191") (pin "2") (pinfunction "2_2") (pintype "passive"))
      (node (ref "C192") (pin "2") (pinfunction "2_2") (pintype "passive"))
      (node (ref "C193") (pin "2") (pinfunction "2_2") (pintype "passive"))
      (node (ref "C194") (pin "2") (pinfunction "2_2") (pintype "passive"))
      (node (ref "C195") (pin "2") (pinfunction "2_2") (pintype "passive"))
      (node (ref "C196") (pin "2") (pinfunction "2_2") (pintype "passive"))
      (node (ref "C197") (pin "2") (pinfunction "2_2") (pintype "passive"))
      (node (ref "C198") (pin "2") (pinfunction "2_2") (pintype "passive"))
      (node (ref "C199") (pin "2") (pinfunction "2_2") (pintype "passive"))
      (node (ref "C200") (pin "2") (pinfunction "2_2") (pintype "passive"))
      (node (ref "C201") (pin "2") (pinfunction "2_2") (pintype "passive"))
      (node (ref "C202") (pin "2") (pinfunction "2_2") (pintype "passive"))
      (node (ref "C248") (pin "2") (pinfunction "2_2") (pintype "passive"))
      (node (ref "C249") (pin "2") (pinfunction "2_2") (pintype "passive"))
      (node (ref "R101") (pin "1") (pinfunction "1_1") (pintype "passive"))
      (node (ref "R102") (pin "1") (pinfunction "1_1") (pintype "passive"))
      (node (ref "R84") (pin "2") (pinfunction "2_2") (pintype "passive"))
      (node (ref "R99") (pin "1") (pinfunction "1_1") (pintype "passive"))
      (node (ref "U8") (pin "13") (pinfunction "VSS_PS_13") (pintype "passive"))
      (node (ref "U8") (pin "29") (pinfunction "VSS_29") (pintype "passive"))
      (node (ref "U8") (pin "49") (pinfunction "P_GND_49") (pintype "passive"))
      (node (ref "U9") (pin "12") (pinfunction "AGND_12") (pintype "passive"))
      (node (ref "U9") (pin "13") (pinfunction "EPAD_13") (pintype "passive"))
      (node (ref "U9") (pin "2") (pinfunction "PGND_2") (pintype "passive"))
    )
    (net (code "50") (name "unconnected-(U8-LDO_O-Pad43)") (class "Default")
      (node (ref "U8") (pin "43") (pinfunction "LDO_O_43") (pintype "passive+no_connect"))
    )
  )
)
